# sx-lok-dec2-328.net
KiCad netlist of a schematic drawn in EAGLE
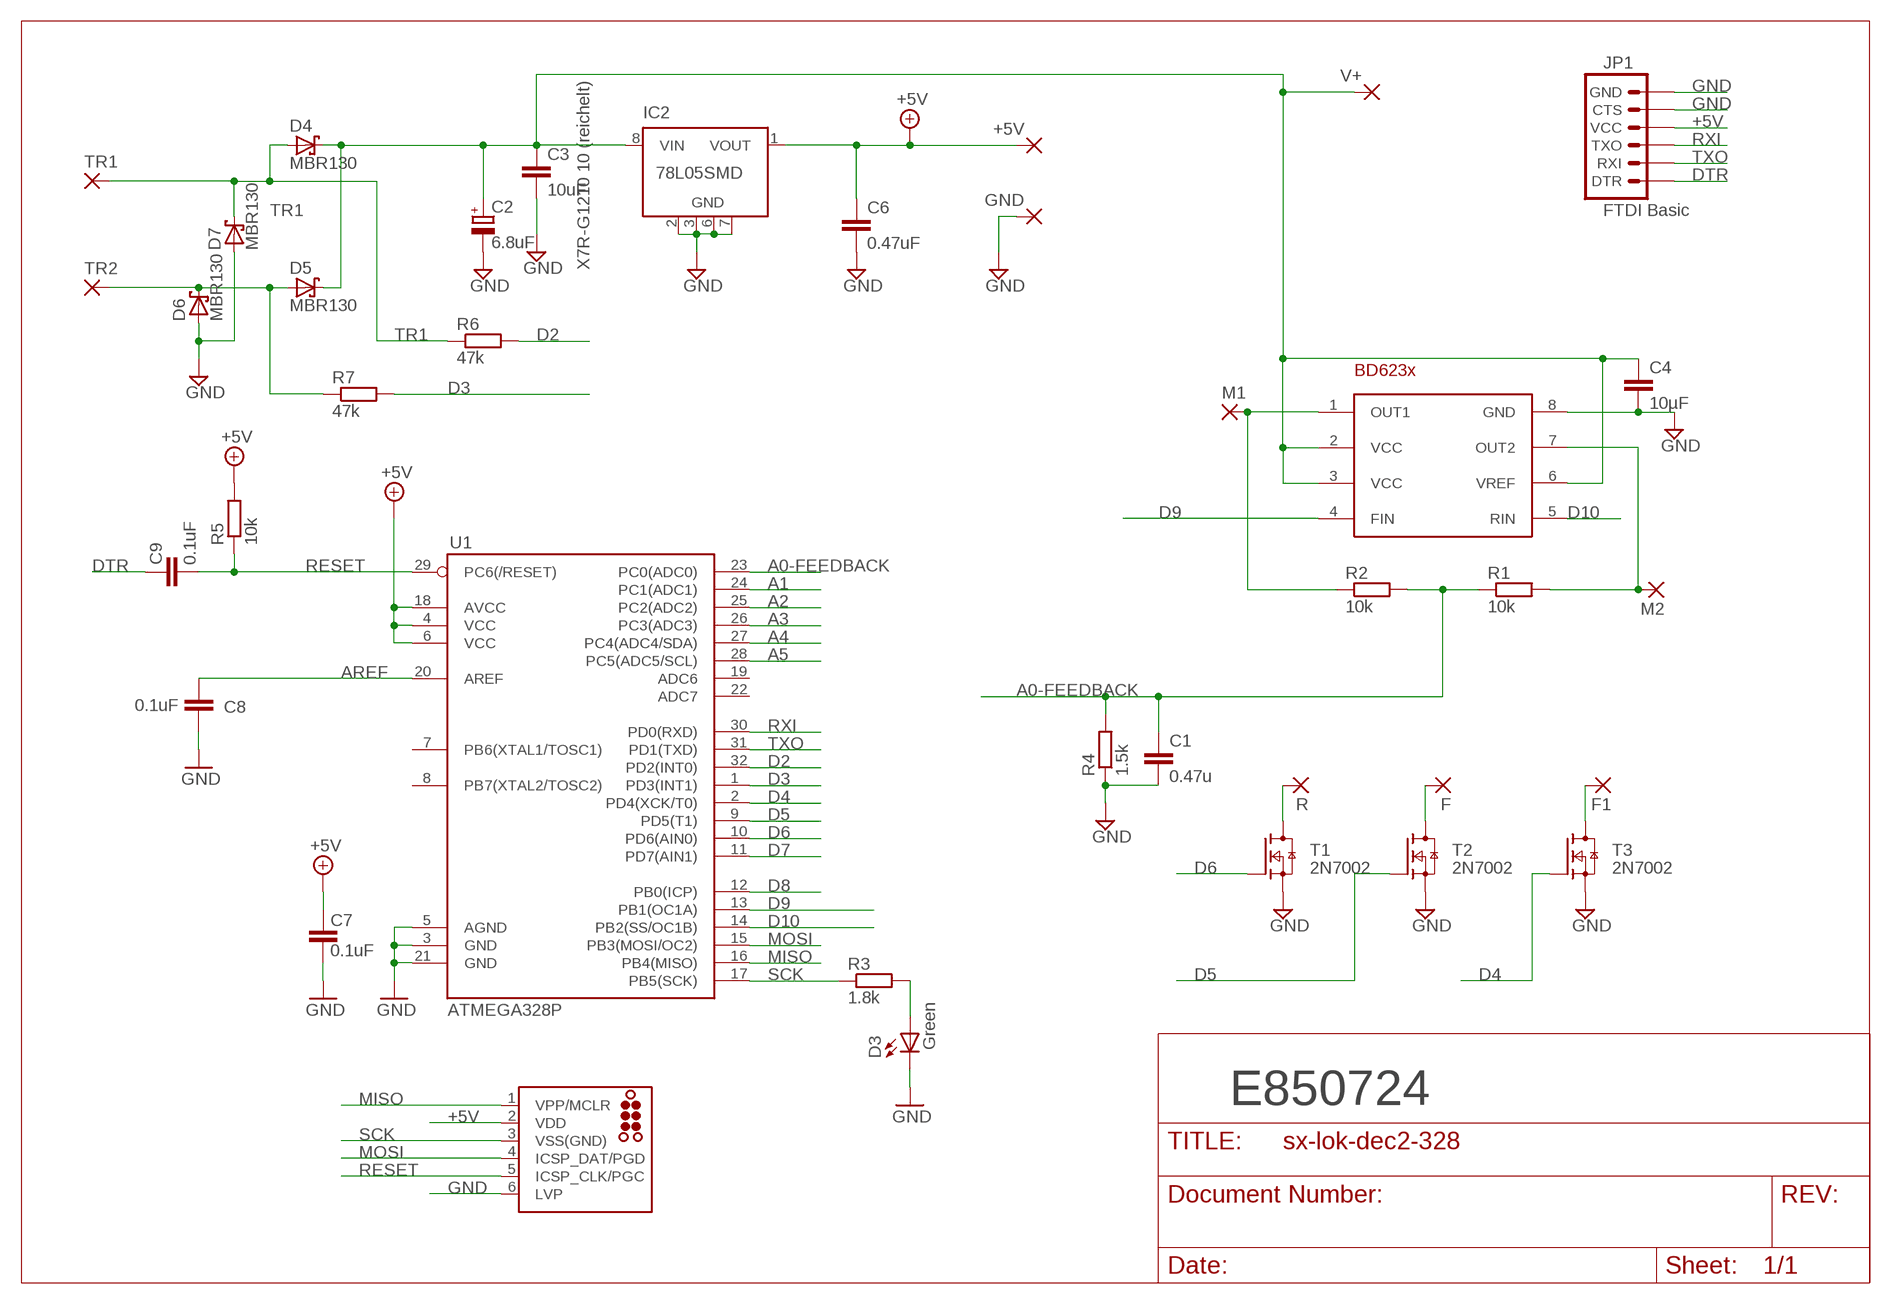
[diagram p0: schematic, sheet 1]

(export (version "E")
  (design (tool "Eeschema 10.0.6"))
  (components
    (comp (ref "+5V")
      (value "SMD2")
      (footprint "eagle-import:SMD1,27-2,54")
      (libsource (lib "eagle-import") (part "SMD2"))
    )
    (comp (ref "BD6231")
      (value "BD6231F")
      (footprint "eagle-import:SOP8")
      (libsource (lib "eagle-import") (part "BD6231F"))
    )
    (comp (ref "C1")
      (value "0.47u")
      (footprint "eagle-import:C1206")
      (libsource (lib "eagle-import") (part "C-EUC1206"))
    )
    (comp (ref "C2")
      (value "6.8uF")
      (footprint "eagle-import:SMC_D")
      (libsource (lib "eagle-import") (part "CPOL-EUSMCD"))
    )
    (comp (ref "C3")
      (value "10uF")
      (footprint "eagle-import:C0805K")
      (libsource (lib "eagle-import") (part "C-EUC0805K"))
    )
    (comp (ref "C4")
      (value "10µF")
      (footprint "eagle-import:C1210K")
      (libsource (lib "eagle-import") (part "C-EUC1210K"))
    )
    (comp (ref "C6")
      (value "0.47uF")
      (footprint "eagle-import:C1206")
      (libsource (lib "eagle-import") (part "C-EUC1206"))
    )
    (comp (ref "C7")
      (value "0.1uF")
      (footprint "eagle-import:0805")
      (libsource (lib "eagle-import") (part "CAP0805"))
    )
    (comp (ref "C8")
      (value "0.1uF")
      (footprint "eagle-import:0805")
      (libsource (lib "eagle-import") (part "CAP0805"))
    )
    (comp (ref "C9")
      (value "0.1uF")
      (footprint "eagle-import:0805")
      (libsource (lib "eagle-import") (part "CAP0805"))
    )
    (comp (ref "D3")
      (value "Green")
      (footprint "eagle-import:LED-0603")
      (libsource (lib "eagle-import") (part "LED0603"))
    )
    (comp (ref "D4")
      (value "MBR130")
      (footprint "eagle-import:SOD123F")
      (libsource (lib "eagle-import") (part "BAS116H"))
    )
    (comp (ref "D5")
      (value "MBR130")
      (footprint "eagle-import:SOD123F")
      (libsource (lib "eagle-import") (part "BAS116H"))
    )
    (comp (ref "D6")
      (value "MBR130")
      (footprint "eagle-import:SOD123F")
      (libsource (lib "eagle-import") (part "BAS116H"))
    )
    (comp (ref "D7")
      (value "MBR130")
      (footprint "eagle-import:SOD123F")
      (libsource (lib "eagle-import") (part "BAS116H"))
    )
    (comp (ref "F")
      (value "SMD2")
      (footprint "eagle-import:SMD1,27-2,54")
      (libsource (lib "eagle-import") (part "SMD2"))
    )
    (comp (ref "F1")
      (value "SMD2")
      (footprint "eagle-import:SMD1,27-2,54")
      (libsource (lib "eagle-import") (part "SMD2"))
    )
    (comp (ref "GND")
      (value "SMD2")
      (footprint "eagle-import:SMD1,27-2,54")
      (libsource (lib "eagle-import") (part "SMD2"))
    )
    (comp (ref "IC2")
      (value "78L05SMD")
      (footprint "eagle-import:SO08")
      (libsource (lib "eagle-import") (part "78LSMD05"))
    )
    (comp (ref "J1")
      (value "ISP")
      (footprint "eagle-import:TC2030-MCP-NL")
      (libsource (lib "eagle-import") (part "TC2030-MCP-NL"))
    )
    (comp (ref "JP1")
      (value "FTDI Basic")
      (footprint "eagle-import:1X06")
      (libsource (lib "eagle-import") (part "ARDUINO_SERIAL_PROGRAMPTH"))
    )
    (comp (ref "M1")
      (value "SMD2")
      (footprint "eagle-import:SMD1,27-2,54")
      (libsource (lib "eagle-import") (part "SMD2"))
    )
    (comp (ref "M2")
      (value "SMD2")
      (footprint "eagle-import:SMD1,27-2,54")
      (libsource (lib "eagle-import") (part "SMD2"))
    )
    (comp (ref "R")
      (value "SMD2")
      (footprint "eagle-import:SMD1,27-2,54")
      (libsource (lib "eagle-import") (part "SMD2"))
    )
    (comp (ref "R1")
      (value "10k")
      (footprint "eagle-import:R0805")
      (libsource (lib "eagle-import") (part "R-EU_R0805"))
    )
    (comp (ref "R2")
      (value "10k")
      (footprint "eagle-import:R0805")
      (libsource (lib "eagle-import") (part "R-EU_R0805"))
    )
    (comp (ref "R3")
      (value "1.8k")
      (footprint "eagle-import:M0805")
      (libsource (lib "eagle-import") (part "R-EU_M0805"))
    )
    (comp (ref "R4")
      (value "1.5k")
      (footprint "eagle-import:R0805")
      (libsource (lib "eagle-import") (part "R-EU_R0805"))
    )
    (comp (ref "R5")
      (value "10k")
      (footprint "eagle-import:M0805")
      (libsource (lib "eagle-import") (part "R-EU_M0805"))
    )
    (comp (ref "R6")
      (value "47k")
      (footprint "eagle-import:R0805")
      (libsource (lib "eagle-import") (part "R-EU_R0805"))
    )
    (comp (ref "R7")
      (value "47k")
      (footprint "eagle-import:M0805")
      (libsource (lib "eagle-import") (part "R-EU_M0805"))
    )
    (comp (ref "T1")
      (value "2N7002")
      (footprint "eagle-import:SOT23")
      (libsource (lib "eagle-import") (part "2N7002E"))
    )
    (comp (ref "T2")
      (value "2N7002")
      (footprint "eagle-import:SOT23")
      (libsource (lib "eagle-import") (part "2N7002E"))
    )
    (comp (ref "T3")
      (value "2N7002")
      (footprint "eagle-import:SOT23")
      (libsource (lib "eagle-import") (part "2N7002E"))
    )
    (comp (ref "TR1")
      (value "SMD2")
      (footprint "eagle-import:SMD1,27-2,54")
      (libsource (lib "eagle-import") (part "SMD2"))
    )
    (comp (ref "TR2")
      (value "SMD2")
      (footprint "eagle-import:SMD1,27-2,54")
      (libsource (lib "eagle-import") (part "SMD2"))
    )
    (comp (ref "U1")
      (value "ATMEGA328P")
      (footprint "eagle-import:TQFP32-08")
      (libsource (lib "eagle-import") (part "ATMEGA168"))
    )
    (comp (ref "V+")
      (value "SMD2")
      (footprint "eagle-import:SMD1,27-2,54")
      (libsource (lib "eagle-import") (part "SMD2"))
    )
  )
  (nets
    (net (code "1") (name "+5V") (class "Default")
      (node (ref "+5V") (pin "1") (pinfunction "P_1") (pintype "passive"))
      (node (ref "C6") (pin "1") (pinfunction "1_1") (pintype "passive"))
      (node (ref "C7") (pin "2") (pinfunction "2_2") (pintype "passive"))
      (node (ref "IC2") (pin "1") (pinfunction "VOUT_1") (pintype "output"))
      (node (ref "J1") (pin "2") (pinfunction "VDD_2") (pintype "power_in"))
      (node (ref "JP1") (pin "4") (pinfunction "VCC_4") (pintype "passive"))
      (node (ref "R5") (pin "2") (pinfunction "2_2") (pintype "passive"))
      (node (ref "U1") (pin "18") (pinfunction "AVCC_18") (pintype "bidirectional"))
      (node (ref "U1") (pin "4") (pinfunction "VCC_4") (pintype "bidirectional"))
      (node (ref "U1") (pin "6") (pinfunction "VCC_6") (pintype "bidirectional"))
    )
    (net (code "2") (name "/A0-FEEDBACK") (class "Default")
      (node (ref "C1") (pin "1") (pinfunction "1_1") (pintype "passive"))
      (node (ref "R1") (pin "1") (pinfunction "1_1") (pintype "passive"))
      (node (ref "R2") (pin "2") (pinfunction "2_2") (pintype "passive"))
      (node (ref "R4") (pin "2") (pinfunction "2_2") (pintype "passive"))
      (node (ref "U1") (pin "23") (pinfunction "PC0(ADC0)_23") (pintype "bidirectional"))
    )
    (net (code "3") (name "/A1") (class "Default")
      (node (ref "U1") (pin "24") (pinfunction "PC1(ADC1)_24") (pintype "bidirectional"))
    )
    (net (code "4") (name "/A2") (class "Default")
      (node (ref "U1") (pin "25") (pinfunction "PC2(ADC2)_25") (pintype "bidirectional"))
    )
    (net (code "5") (name "/A3") (class "Default")
      (node (ref "U1") (pin "26") (pinfunction "PC3(ADC3)_26") (pintype "bidirectional"))
    )
    (net (code "6") (name "/A4") (class "Default")
      (node (ref "U1") (pin "27") (pinfunction "PC4(ADC4/SDA)_27") (pintype "bidirectional"))
    )
    (net (code "7") (name "/A5") (class "Default")
      (node (ref "U1") (pin "28") (pinfunction "PC5(ADC5/SCL)_28") (pintype "bidirectional"))
    )
    (net (code "8") (name "/AREF") (class "Default")
      (node (ref "C8") (pin "2") (pinfunction "2_2") (pintype "passive"))
      (node (ref "U1") (pin "20") (pinfunction "AREF_20") (pintype "bidirectional"))
    )
    (net (code "9") (name "/D2") (class "Default")
      (node (ref "R6") (pin "2") (pinfunction "2_2") (pintype "passive"))
      (node (ref "U1") (pin "32") (pinfunction "PD2(INT0)_32") (pintype "bidirectional"))
    )
    (net (code "10") (name "/D3") (class "Default")
      (node (ref "R7") (pin "2") (pinfunction "2_2") (pintype "passive"))
      (node (ref "U1") (pin "1") (pinfunction "PD3(INT1)_1") (pintype "bidirectional"))
    )
    (net (code "11") (name "/D4") (class "Default")
      (node (ref "T3") (pin "1") (pinfunction "G_1") (pintype "passive"))
      (node (ref "U1") (pin "2") (pinfunction "PD4(XCK/T0)_2") (pintype "bidirectional"))
    )
    (net (code "12") (name "/D5") (class "Default")
      (node (ref "T2") (pin "1") (pinfunction "G_1") (pintype "passive"))
      (node (ref "U1") (pin "9") (pinfunction "PD5(T1)_9") (pintype "bidirectional"))
    )
    (net (code "13") (name "/D6") (class "Default")
      (node (ref "T1") (pin "1") (pinfunction "G_1") (pintype "passive"))
      (node (ref "U1") (pin "10") (pinfunction "PD6(AIN0)_10") (pintype "bidirectional"))
    )
    (net (code "14") (name "/D7") (class "Default")
      (node (ref "U1") (pin "11") (pinfunction "PD7(AIN1)_11") (pintype "bidirectional"))
    )
    (net (code "15") (name "/D8") (class "Default")
      (node (ref "U1") (pin "12") (pinfunction "PB0(ICP)_12") (pintype "bidirectional"))
    )
    (net (code "16") (name "/D9") (class "Default")
      (node (ref "BD6231") (pin "4") (pinfunction "FIN_4") (pintype "bidirectional"))
      (node (ref "U1") (pin "13") (pinfunction "PB1(OC1A)_13") (pintype "bidirectional"))
    )
    (net (code "17") (name "/D10") (class "Default")
      (node (ref "BD6231") (pin "5") (pinfunction "RIN_5") (pintype "bidirectional"))
      (node (ref "U1") (pin "14") (pinfunction "PB2(SS/OC1B)_14") (pintype "bidirectional"))
    )
    (net (code "18") (name "/DTR") (class "Default")
      (node (ref "C9") (pin "2") (pinfunction "2_2") (pintype "passive"))
      (node (ref "JP1") (pin "1") (pinfunction "DTR_1") (pintype "passive"))
    )
    (net (code "19") (name "/MISO") (class "Default")
      (node (ref "J1") (pin "1") (pinfunction "VPP/MCLR_1") (pintype "passive"))
      (node (ref "U1") (pin "16") (pinfunction "PB4(MISO)_16") (pintype "bidirectional"))
    )
    (net (code "20") (name "/MOSI") (class "Default")
      (node (ref "J1") (pin "4") (pinfunction "ICSP_DAT/PGD_4") (pintype "bidirectional"))
      (node (ref "U1") (pin "15") (pinfunction "PB3(MOSI/OC2)_15") (pintype "bidirectional"))
    )
    (net (code "21") (name "/RESET") (class "Default")
      (node (ref "C9") (pin "1") (pinfunction "1_1") (pintype "passive"))
      (node (ref "J1") (pin "5") (pinfunction "ICSP_CLK/PGC_5") (pintype "output"))
      (node (ref "R5") (pin "1") (pinfunction "1_1") (pintype "passive"))
      (node (ref "U1") (pin "29") (pinfunction "PC6(/RESET)_29") (pintype "bidirectional"))
    )
    (net (code "22") (name "/RXI") (class "Default")
      (node (ref "JP1") (pin "3") (pinfunction "TXO_3") (pintype "passive"))
      (node (ref "U1") (pin "30") (pinfunction "PD0(RXD)_30") (pintype "bidirectional"))
    )
    (net (code "23") (name "/SCK") (class "Default")
      (node (ref "J1") (pin "3") (pinfunction "VSS(GND)_3") (pintype "power_in"))
      (node (ref "R3") (pin "1") (pinfunction "1_1") (pintype "passive"))
      (node (ref "U1") (pin "17") (pinfunction "PB5(SCK)_17") (pintype "bidirectional"))
    )
    (net (code "24") (name "/TR1") (class "Default")
      (node (ref "D4") (pin "2") (pinfunction "A_2") (pintype "passive"))
      (node (ref "D7") (pin "1") (pinfunction "K_1") (pintype "passive"))
      (node (ref "R6") (pin "1") (pinfunction "1_1") (pintype "passive"))
      (node (ref "TR1") (pin "1") (pinfunction "P_1") (pintype "passive"))
    )
    (net (code "25") (name "/TXO") (class "Default")
      (node (ref "JP1") (pin "2") (pinfunction "RXI_2") (pintype "passive"))
      (node (ref "U1") (pin "31") (pinfunction "PD1(TXD)_31") (pintype "bidirectional"))
    )
    (net (code "26") (name "GND") (class "Default")
      (node (ref "BD6231") (pin "8") (pinfunction "GND_8") (pintype "power_in"))
      (node (ref "C1") (pin "2") (pinfunction "2_2") (pintype "passive"))
      (node (ref "C2") (pin "-") (pinfunction "-_-") (pintype "passive"))
      (node (ref "C3") (pin "2") (pinfunction "2_2") (pintype "passive"))
      (node (ref "C4") (pin "2") (pinfunction "2_2") (pintype "passive"))
      (node (ref "C6") (pin "2") (pinfunction "2_2") (pintype "passive"))
      (node (ref "C7") (pin "1") (pinfunction "1_1") (pintype "passive"))
      (node (ref "C8") (pin "1") (pinfunction "1_1") (pintype "passive"))
      (node (ref "D3") (pin "C") (pinfunction "C_C") (pintype "passive"))
      (node (ref "D6") (pin "2") (pinfunction "A_2") (pintype "passive"))
      (node (ref "D7") (pin "2") (pinfunction "A_2") (pintype "passive"))
      (node (ref "GND") (pin "1") (pinfunction "P_1") (pintype "passive"))
      (node (ref "IC2") (pin "2") (pinfunction "GND_2") (pintype "power_in"))
      (node (ref "IC2") (pin "3") (pinfunction "GND_3") (pintype "power_in"))
      (node (ref "IC2") (pin "6") (pinfunction "GND_6") (pintype "power_in"))
      (node (ref "IC2") (pin "7") (pinfunction "GND_7") (pintype "power_in"))
      (node (ref "J1") (pin "6") (pinfunction "LVP_6") (pintype "bidirectional"))
      (node (ref "JP1") (pin "5") (pinfunction "CTS_5") (pintype "passive"))
      (node (ref "JP1") (pin "6") (pinfunction "GND_6") (pintype "passive"))
      (node (ref "R4") (pin "1") (pinfunction "1_1") (pintype "passive"))
      (node (ref "T1") (pin "2") (pinfunction "S_2") (pintype "passive"))
      (node (ref "T2") (pin "2") (pinfunction "S_2") (pintype "passive"))
      (node (ref "T3") (pin "2") (pinfunction "S_2") (pintype "passive"))
      (node (ref "U1") (pin "21") (pinfunction "GND_21") (pintype "bidirectional"))
      (node (ref "U1") (pin "3") (pinfunction "GND_3") (pintype "bidirectional"))
      (node (ref "U1") (pin "5") (pinfunction "AGND_5") (pintype "bidirectional"))
    )
    (net (code "27") (name "Net-(BD6231-OUT1)") (class "Default")
      (node (ref "BD6231") (pin "1") (pinfunction "OUT1_1") (pintype "bidirectional"))
      (node (ref "M1") (pin "1") (pinfunction "P_1") (pintype "passive"))
      (node (ref "R2") (pin "1") (pinfunction "1_1") (pintype "passive"))
    )
    (net (code "28") (name "Net-(BD6231-OUT2)") (class "Default")
      (node (ref "BD6231") (pin "7") (pinfunction "OUT2_7") (pintype "bidirectional"))
      (node (ref "M2") (pin "1") (pinfunction "P_1") (pintype "passive"))
      (node (ref "R1") (pin "2") (pinfunction "2_2") (pintype "passive"))
    )
    (net (code "29") (name "Net-(BD6231-VREF)") (class "Default")
      (node (ref "BD6231") (pin "2") (pinfunction "VCC_2") (pintype "power_in"))
      (node (ref "BD6231") (pin "3") (pinfunction "VCC_3") (pintype "power_in"))
      (node (ref "BD6231") (pin "6") (pinfunction "VREF_6") (pintype "bidirectional"))
      (node (ref "C2") (pin "+") (pinfunction "+_+") (pintype "passive"))
      (node (ref "C3") (pin "1") (pinfunction "1_1") (pintype "passive"))
      (node (ref "C4") (pin "1") (pinfunction "1_1") (pintype "passive"))
      (node (ref "D4") (pin "1") (pinfunction "K_1") (pintype "passive"))
      (node (ref "D5") (pin "1") (pinfunction "K_1") (pintype "passive"))
      (node (ref "IC2") (pin "8") (pinfunction "VIN_8") (pintype "passive"))
      (node (ref "V+") (pin "1") (pinfunction "P_1") (pintype "passive"))
    )
    (net (code "30") (name "Net-(D3-PadA)") (class "Default")
      (node (ref "D3") (pin "A") (pinfunction "A_A") (pintype "passive"))
      (node (ref "R3") (pin "2") (pinfunction "2_2") (pintype "passive"))
    )
    (net (code "31") (name "Net-(D5-A)") (class "Default")
      (node (ref "D5") (pin "2") (pinfunction "A_2") (pintype "passive"))
      (node (ref "D6") (pin "1") (pinfunction "K_1") (pintype "passive"))
      (node (ref "R7") (pin "1") (pinfunction "1_1") (pintype "passive"))
      (node (ref "TR2") (pin "1") (pinfunction "P_1") (pintype "passive"))
    )
    (net (code "32") (name "Net-(F-P)") (class "Default")
      (node (ref "F") (pin "1") (pinfunction "P_1") (pintype "passive"))
      (node (ref "T2") (pin "3") (pinfunction "D_3") (pintype "passive"))
    )
    (net (code "33") (name "Net-(F1-P)") (class "Default")
      (node (ref "F1") (pin "1") (pinfunction "P_1") (pintype "passive"))
      (node (ref "T3") (pin "3") (pinfunction "D_3") (pintype "passive"))
    )
    (net (code "34") (name "Net-(R-P)") (class "Default")
      (node (ref "R") (pin "1") (pinfunction "P_1") (pintype "passive"))
      (node (ref "T1") (pin "3") (pinfunction "D_3") (pintype "passive"))
    )
    (net (code "35") (name "unconnected-(U1-ADC6-Pad19)") (class "Default")
      (node (ref "U1") (pin "19") (pinfunction "ADC6_19") (pintype "bidirectional"))
    )
    (net (code "36") (name "unconnected-(U1-ADC7-Pad22)") (class "Default")
      (node (ref "U1") (pin "22") (pinfunction "ADC7_22") (pintype "bidirectional"))
    )
    (net (code "37") (name "unconnected-(U1-PB6(XTAL1{slash}TOSC1)-Pad7)") (class "Default")
      (node (ref "U1") (pin "7") (pinfunction "PB6(XTAL1/TOSC1)_7") (pintype "bidirectional"))
    )
    (net (code "38") (name "unconnected-(U1-PB7(XTAL2{slash}TOSC2)-Pad8)") (class "Default")
      (node (ref "U1") (pin "8") (pinfunction "PB7(XTAL2/TOSC2)_8") (pintype "bidirectional"))
    )
  )
)
